# pcb_power.net
KiCad netlist of a schematic drawn in EAGLE
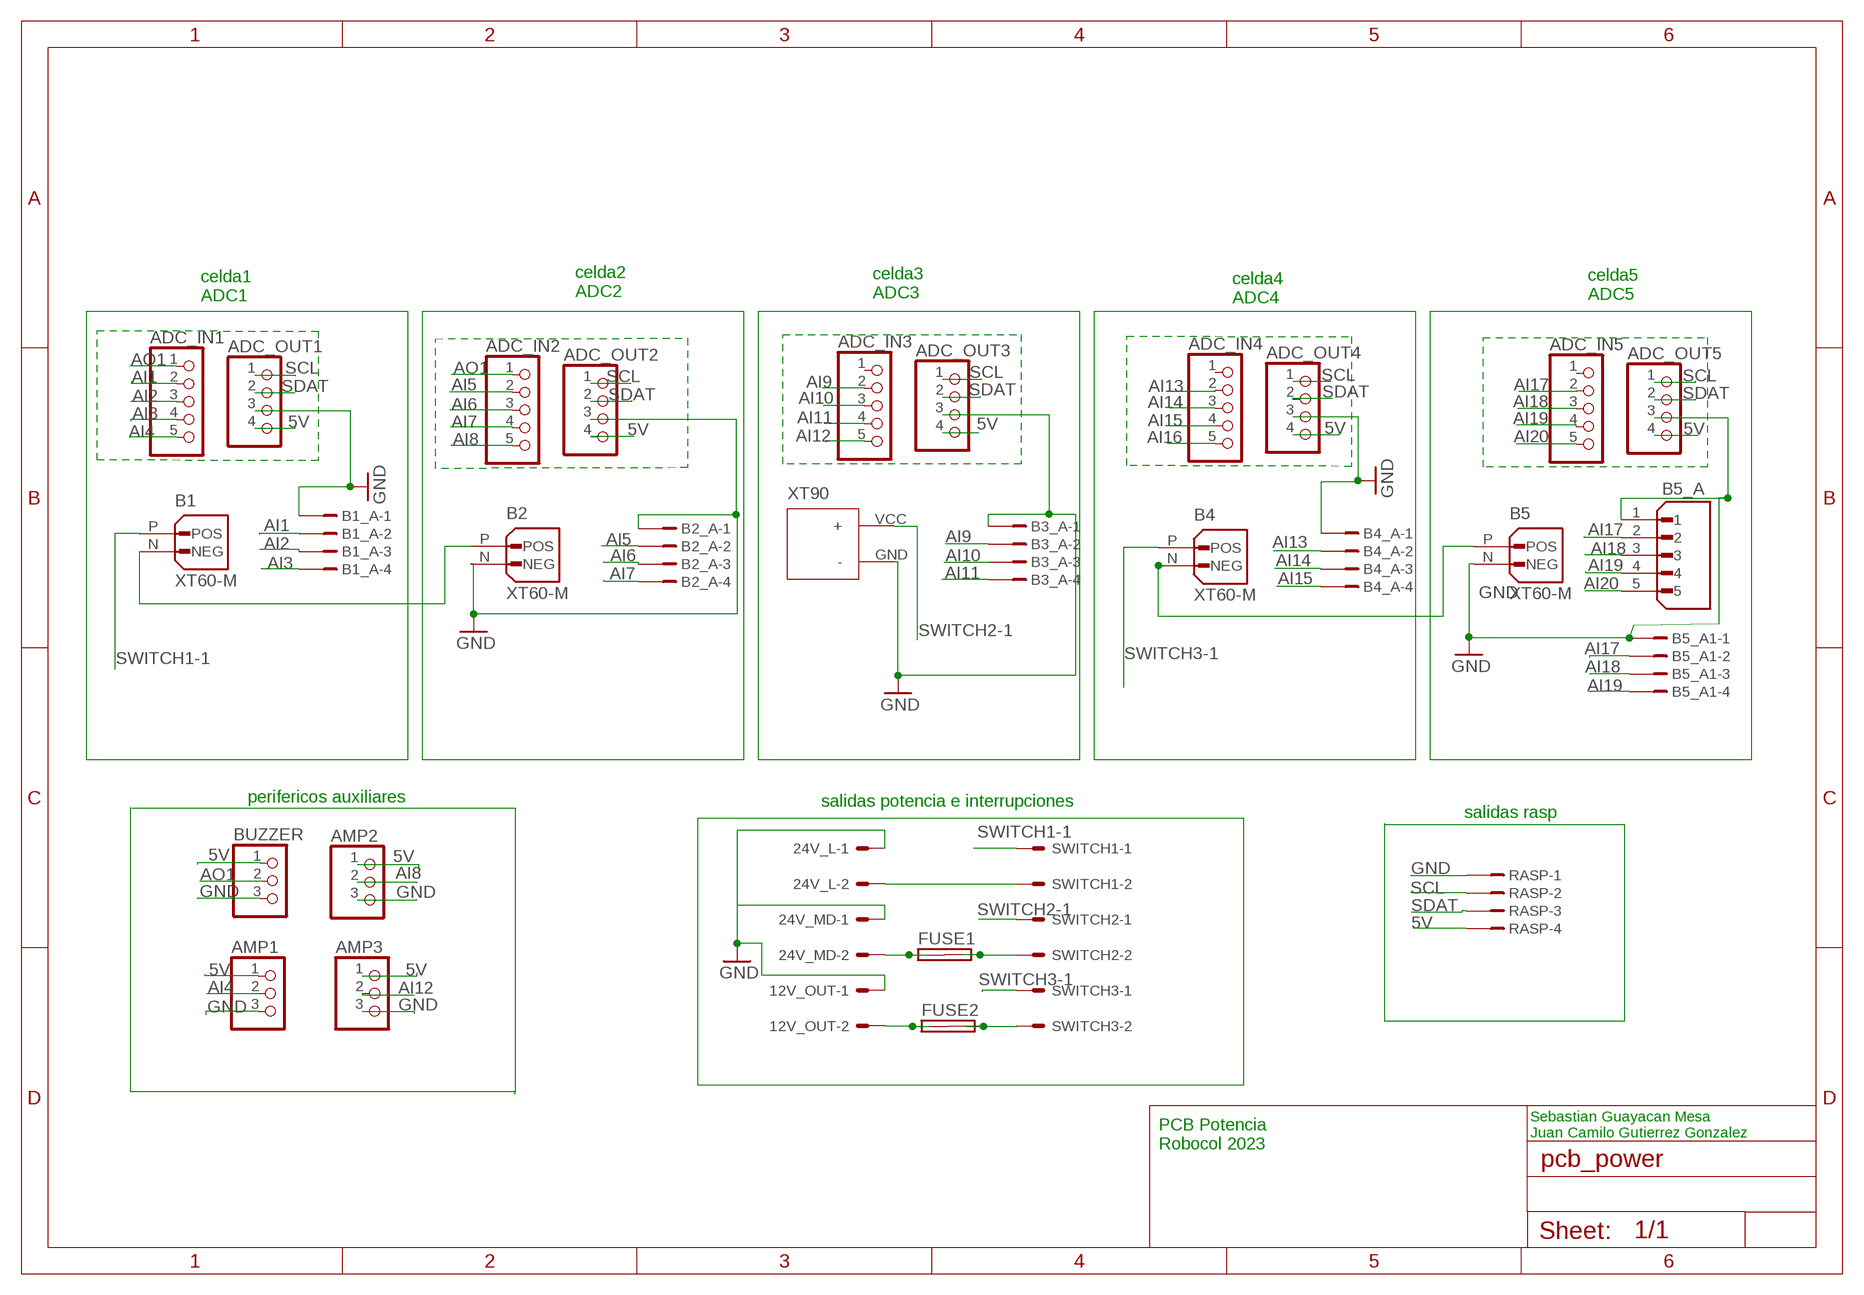
[diagram p0: schematic, sheet 1]

(export (version "E")
  (design (tool "Eeschema 10.0.6"))
  (components
    (comp (ref "12V_OUT")
      (value "5566-25569-2")
      (footprint "eagle-import:5569-2")
      (libsource (lib "eagle-import") (part "5566-25569-2"))
    )
    (comp (ref "24V_L")
      (value "5566-25569-2")
      (footprint "eagle-import:5569-2")
      (libsource (lib "eagle-import") (part "5566-25569-2"))
    )
    (comp (ref "24V_MD")
      (value "5566-25569-2")
      (footprint "eagle-import:5569-2")
      (libsource (lib "eagle-import") (part "5566-25569-2"))
    )
    (comp (ref "ADC_IN1")
      (value "PINHD-1X5")
      (footprint "eagle-import:1X05")
      (libsource (lib "eagle-import") (part "PINHD-1X5"))
    )
    (comp (ref "ADC_IN2")
      (value "PINHD-1X5")
      (footprint "eagle-import:1X05")
      (libsource (lib "eagle-import") (part "PINHD-1X5"))
    )
    (comp (ref "ADC_IN3")
      (value "PINHD-1X5")
      (footprint "eagle-import:1X05")
      (libsource (lib "eagle-import") (part "PINHD-1X5"))
    )
    (comp (ref "ADC_IN4")
      (value "PINHD-1X5")
      (footprint "eagle-import:1X05")
      (libsource (lib "eagle-import") (part "PINHD-1X5"))
    )
    (comp (ref "ADC_IN5")
      (value "PINHD-1X5")
      (footprint "eagle-import:1X05")
      (libsource (lib "eagle-import") (part "PINHD-1X5"))
    )
    (comp (ref "ADC_OUT1")
      (value "PINHD-1X4")
      (footprint "eagle-import:1X04")
      (libsource (lib "eagle-import") (part "PINHD-1X4"))
    )
    (comp (ref "ADC_OUT2")
      (value "PINHD-1X4")
      (footprint "eagle-import:1X04")
      (libsource (lib "eagle-import") (part "PINHD-1X4"))
    )
    (comp (ref "ADC_OUT3")
      (value "PINHD-1X4")
      (footprint "eagle-import:1X04")
      (libsource (lib "eagle-import") (part "PINHD-1X4"))
    )
    (comp (ref "ADC_OUT4")
      (value "PINHD-1X4")
      (footprint "eagle-import:1X04")
      (libsource (lib "eagle-import") (part "PINHD-1X4"))
    )
    (comp (ref "ADC_OUT5")
      (value "PINHD-1X4")
      (footprint "eagle-import:1X04")
      (libsource (lib "eagle-import") (part "PINHD-1X4"))
    )
    (comp (ref "AMP1")
      (value "PINHD-1X3")
      (footprint "eagle-import:1X03")
      (libsource (lib "eagle-import") (part "PINHD-1X3"))
    )
    (comp (ref "AMP2")
      (value "PINHD-1X3")
      (footprint "eagle-import:1X03")
      (libsource (lib "eagle-import") (part "PINHD-1X3"))
    )
    (comp (ref "AMP3")
      (value "PINHD-1X3")
      (footprint "eagle-import:1X03")
      (libsource (lib "eagle-import") (part "PINHD-1X3"))
    )
    (comp (ref "B1")
      (value "XT60-M")
      (footprint "eagle-import:AMASS_XT60-M")
      (fields (field (name "MF") "AMASS"))
      (libsource (lib "eagle-import") (part "XT60-M"))
    )
    (comp (ref "B1_A")
      (value "B4B-ZR")
      (footprint "eagle-import:B4B-ZR")
      (fields (field (name "MF") "FARNELL") (field (name "MPN") "B4B-ZR(LF)(SN)"))
      (libsource (lib "eagle-import") (part "?4B-ZRB"))
    )
    (comp (ref "B2")
      (value "XT60-M")
      (footprint "eagle-import:AMASS_XT60-M")
      (fields (field (name "MF") "AMASS"))
      (libsource (lib "eagle-import") (part "XT60-M"))
    )
    (comp (ref "B2_A")
      (value "B4B-ZR")
      (footprint "eagle-import:B4B-ZR")
      (fields (field (name "MF") "FARNELL") (field (name "MPN") "B4B-ZR(LF)(SN)"))
      (libsource (lib "eagle-import") (part "?4B-ZRB"))
    )
    (comp (ref "B3")
      (value "XT90")
      (footprint "eagle-import:XT90_PADS")
      (libsource (lib "eagle-import") (part "XT90"))
    )
    (comp (ref "B3_A")
      (value "B4B-ZR")
      (footprint "eagle-import:B4B-ZR")
      (fields (field (name "MF") "FARNELL") (field (name "MPN") "B4B-ZR(LF)(SN)"))
      (libsource (lib "eagle-import") (part "?4B-ZRB"))
    )
    (comp (ref "B4")
      (value "XT60-M")
      (footprint "eagle-import:AMASS_XT60-M")
      (fields (field (name "MF") "AMASS"))
      (libsource (lib "eagle-import") (part "XT60-M"))
    )
    (comp (ref "B4_A")
      (value "B4B-ZR")
      (footprint "eagle-import:B4B-ZR")
      (fields (field (name "MF") "FARNELL") (field (name "MPN") "B4B-ZR(LF)(SN)"))
      (libsource (lib "eagle-import") (part "?4B-ZRB"))
    )
    (comp (ref "B5")
      (value "XT60-M")
      (footprint "eagle-import:AMASS_XT60-M")
      (fields (field (name "MF") "AMASS"))
      (libsource (lib "eagle-import") (part "XT60-M"))
    )
    (comp (ref "B5_A")
      (value "B5B-ZR(LF)(SN)")
      (footprint "eagle-import:JST_B5B-ZR(LF)(SN)")
      (fields (field (name "MF") "JST") (field (name "MP") "B5B-ZR (LF)(SN)"))
      (libsource (lib "eagle-import") (part "B5B-ZR(LF)(SN)"))
    )
    (comp (ref "B5_A1")
      (value "B4B-ZR")
      (footprint "eagle-import:B4B-ZR")
      (fields (field (name "MF") "FARNELL") (field (name "MPN") "B4B-ZR(LF)(SN)"))
      (libsource (lib "eagle-import") (part "?4B-ZRB"))
    )
    (comp (ref "BUZZER")
      (value "PINHD-1X3")
      (footprint "eagle-import:1X03")
      (libsource (lib "eagle-import") (part "PINHD-1X3"))
    )
    (comp (ref "FUSE1")
      (value "SHK20L")
      (footprint "eagle-import:SHK20L")
      (libsource (lib "eagle-import") (part "SHK20L"))
    )
    (comp (ref "FUSE2")
      (value "SHK20L")
      (footprint "eagle-import:SHK20L")
      (libsource (lib "eagle-import") (part "SHK20L"))
    )
    (comp (ref "RASP")
      (value "B4B-ZR")
      (footprint "eagle-import:B4B-ZR")
      (fields (field (name "MF") "FARNELL") (field (name "MPN") "B4B-ZR(LF)(SN)"))
      (libsource (lib "eagle-import") (part "?4B-ZRB"))
    )
    (comp (ref "SWITCH1")
      (value "5566-25569-2")
      (footprint "eagle-import:5569-2")
      (libsource (lib "eagle-import") (part "5566-25569-2"))
    )
    (comp (ref "SWITCH2")
      (value "5566-25569-2")
      (footprint "eagle-import:5569-2")
      (libsource (lib "eagle-import") (part "5566-25569-2"))
    )
    (comp (ref "SWITCH3")
      (value "5566-25569-2")
      (footprint "eagle-import:5569-2")
      (libsource (lib "eagle-import") (part "5566-25569-2"))
    )
  )
  (nets
    (net (code "1") (name "/5V") (class "Default")
      (node (ref "ADC_OUT1") (pin "4") (pinfunction "4_4") (pintype "passive"))
      (node (ref "ADC_OUT2") (pin "4") (pinfunction "4_4") (pintype "passive"))
      (node (ref "ADC_OUT3") (pin "4") (pinfunction "4_4") (pintype "passive"))
      (node (ref "ADC_OUT4") (pin "4") (pinfunction "4_4") (pintype "passive"))
      (node (ref "ADC_OUT5") (pin "4") (pinfunction "4_4") (pintype "passive"))
      (node (ref "AMP1") (pin "1") (pinfunction "1_1") (pintype "passive"))
      (node (ref "AMP2") (pin "1") (pinfunction "1_1") (pintype "passive"))
      (node (ref "AMP3") (pin "1") (pinfunction "1_1") (pintype "passive"))
      (node (ref "BUZZER") (pin "1") (pinfunction "1_1") (pintype "passive"))
      (node (ref "RASP") (pin "4") (pinfunction "1_4") (pintype "passive"))
    )
    (net (code "2") (name "/AI1") (class "Default")
      (node (ref "ADC_IN1") (pin "2") (pinfunction "2_2") (pintype "passive"))
      (node (ref "B1_A") (pin "2") (pinfunction "1_2") (pintype "passive"))
    )
    (net (code "3") (name "/AI2") (class "Default")
      (node (ref "ADC_IN1") (pin "3") (pinfunction "3_3") (pintype "passive"))
      (node (ref "B1_A") (pin "3") (pinfunction "1_3") (pintype "passive"))
    )
    (net (code "4") (name "/AI3") (class "Default")
      (node (ref "ADC_IN1") (pin "4") (pinfunction "4_4") (pintype "passive"))
      (node (ref "B1_A") (pin "4") (pinfunction "1_4") (pintype "passive"))
    )
    (net (code "5") (name "/AI4") (class "Default")
      (node (ref "ADC_IN1") (pin "5") (pinfunction "5_5") (pintype "passive"))
      (node (ref "AMP1") (pin "2") (pinfunction "2_2") (pintype "passive"))
    )
    (net (code "6") (name "/AI5") (class "Default")
      (node (ref "ADC_IN2") (pin "2") (pinfunction "2_2") (pintype "passive"))
      (node (ref "B2_A") (pin "2") (pinfunction "1_2") (pintype "passive"))
    )
    (net (code "7") (name "/AI6") (class "Default")
      (node (ref "ADC_IN2") (pin "3") (pinfunction "3_3") (pintype "passive"))
      (node (ref "B2_A") (pin "3") (pinfunction "1_3") (pintype "passive"))
    )
    (net (code "8") (name "/AI7") (class "Default")
      (node (ref "ADC_IN2") (pin "4") (pinfunction "4_4") (pintype "passive"))
      (node (ref "B2_A") (pin "4") (pinfunction "1_4") (pintype "passive"))
    )
    (net (code "9") (name "/AI8") (class "Default")
      (node (ref "ADC_IN2") (pin "5") (pinfunction "5_5") (pintype "passive"))
      (node (ref "AMP2") (pin "2") (pinfunction "2_2") (pintype "passive"))
    )
    (net (code "10") (name "/AI9") (class "Default")
      (node (ref "ADC_IN3") (pin "2") (pinfunction "2_2") (pintype "passive"))
      (node (ref "B3_A") (pin "2") (pinfunction "1_2") (pintype "passive"))
    )
    (net (code "11") (name "/AI10") (class "Default")
      (node (ref "ADC_IN3") (pin "3") (pinfunction "3_3") (pintype "passive"))
      (node (ref "B3_A") (pin "3") (pinfunction "1_3") (pintype "passive"))
    )
    (net (code "12") (name "/AI11") (class "Default")
      (node (ref "ADC_IN3") (pin "4") (pinfunction "4_4") (pintype "passive"))
      (node (ref "B3_A") (pin "4") (pinfunction "1_4") (pintype "passive"))
    )
    (net (code "13") (name "/AI12") (class "Default")
      (node (ref "ADC_IN3") (pin "5") (pinfunction "5_5") (pintype "passive"))
      (node (ref "AMP3") (pin "2") (pinfunction "2_2") (pintype "passive"))
    )
    (net (code "14") (name "/AI13") (class "Default")
      (node (ref "ADC_IN4") (pin "2") (pinfunction "2_2") (pintype "passive"))
      (node (ref "B4_A") (pin "2") (pinfunction "1_2") (pintype "passive"))
    )
    (net (code "15") (name "/AI14") (class "Default")
      (node (ref "ADC_IN4") (pin "3") (pinfunction "3_3") (pintype "passive"))
      (node (ref "B4_A") (pin "3") (pinfunction "1_3") (pintype "passive"))
    )
    (net (code "16") (name "/AI15") (class "Default")
      (node (ref "ADC_IN4") (pin "4") (pinfunction "4_4") (pintype "passive"))
      (node (ref "B4_A") (pin "4") (pinfunction "1_4") (pintype "passive"))
    )
    (net (code "17") (name "/AI16") (class "Default")
      (node (ref "ADC_IN4") (pin "5") (pinfunction "5_5") (pintype "passive"))
    )
    (net (code "18") (name "/AI17") (class "Default")
      (node (ref "ADC_IN5") (pin "2") (pinfunction "2_2") (pintype "passive"))
      (node (ref "B5_A") (pin "2") (pinfunction "2_2") (pintype "passive"))
      (node (ref "B5_A1") (pin "2") (pinfunction "1_2") (pintype "passive"))
    )
    (net (code "19") (name "/AI18") (class "Default")
      (node (ref "ADC_IN5") (pin "3") (pinfunction "3_3") (pintype "passive"))
      (node (ref "B5_A") (pin "3") (pinfunction "3_3") (pintype "passive"))
      (node (ref "B5_A1") (pin "3") (pinfunction "1_3") (pintype "passive"))
    )
    (net (code "20") (name "/AI19") (class "Default")
      (node (ref "ADC_IN5") (pin "4") (pinfunction "4_4") (pintype "passive"))
      (node (ref "B5_A") (pin "4") (pinfunction "4_4") (pintype "passive"))
      (node (ref "B5_A1") (pin "4") (pinfunction "1_4") (pintype "passive"))
    )
    (net (code "21") (name "/AI20") (class "Default")
      (node (ref "ADC_IN5") (pin "5") (pinfunction "5_5") (pintype "passive"))
      (node (ref "B5_A") (pin "5") (pinfunction "5_5") (pintype "passive"))
    )
    (net (code "22") (name "/AO1") (class "Default")
      (node (ref "ADC_IN1") (pin "1") (pinfunction "1_1") (pintype "passive"))
      (node (ref "ADC_IN2") (pin "1") (pinfunction "1_1") (pintype "passive"))
      (node (ref "BUZZER") (pin "2") (pinfunction "2_2") (pintype "passive"))
    )
    (net (code "23") (name "/SCL") (class "Default")
      (node (ref "ADC_OUT1") (pin "1") (pinfunction "1_1") (pintype "passive"))
      (node (ref "ADC_OUT2") (pin "1") (pinfunction "1_1") (pintype "passive"))
      (node (ref "ADC_OUT3") (pin "1") (pinfunction "1_1") (pintype "passive"))
      (node (ref "ADC_OUT4") (pin "1") (pinfunction "1_1") (pintype "passive"))
      (node (ref "ADC_OUT5") (pin "1") (pinfunction "1_1") (pintype "passive"))
      (node (ref "RASP") (pin "2") (pinfunction "1_2") (pintype "passive"))
    )
    (net (code "24") (name "/SDAT") (class "Default")
      (node (ref "ADC_OUT1") (pin "2") (pinfunction "2_2") (pintype "passive"))
      (node (ref "ADC_OUT2") (pin "2") (pinfunction "2_2") (pintype "passive"))
      (node (ref "ADC_OUT3") (pin "2") (pinfunction "2_2") (pintype "passive"))
      (node (ref "ADC_OUT4") (pin "2") (pinfunction "2_2") (pintype "passive"))
      (node (ref "ADC_OUT5") (pin "2") (pinfunction "2_2") (pintype "passive"))
      (node (ref "RASP") (pin "3") (pinfunction "1_3") (pintype "passive"))
    )
    (net (code "25") (name "/SWITCH1-1") (class "Default")
      (node (ref "B1") (pin "P") (pinfunction "POS_P") (pintype "passive"))
      (node (ref "SWITCH1") (pin "1") (pinfunction "S_1") (pintype "passive"))
    )
    (net (code "26") (name "/SWITCH2-1") (class "Default")
      (node (ref "B3") (pin "VCC") (pinfunction "+_VCC") (pintype "power_in"))
      (node (ref "SWITCH2") (pin "1") (pinfunction "S_1") (pintype "passive"))
    )
    (net (code "27") (name "/SWITCH3-1") (class "Default")
      (node (ref "B4") (pin "P") (pinfunction "POS_P") (pintype "passive"))
      (node (ref "SWITCH3") (pin "1") (pinfunction "S_1") (pintype "passive"))
    )
    (net (code "28") (name "GND") (class "Default")
      (node (ref "12V_OUT") (pin "1") (pinfunction "S_1") (pintype "passive"))
      (node (ref "24V_L") (pin "1") (pinfunction "S_1") (pintype "passive"))
      (node (ref "24V_MD") (pin "1") (pinfunction "S_1") (pintype "passive"))
      (node (ref "ADC_OUT1") (pin "3") (pinfunction "3_3") (pintype "passive"))
      (node (ref "ADC_OUT2") (pin "3") (pinfunction "3_3") (pintype "passive"))
      (node (ref "ADC_OUT3") (pin "3") (pinfunction "3_3") (pintype "passive"))
      (node (ref "ADC_OUT4") (pin "3") (pinfunction "3_3") (pintype "passive"))
      (node (ref "ADC_OUT5") (pin "3") (pinfunction "3_3") (pintype "passive"))
      (node (ref "AMP1") (pin "3") (pinfunction "3_3") (pintype "passive"))
      (node (ref "AMP2") (pin "3") (pinfunction "3_3") (pintype "passive"))
      (node (ref "AMP3") (pin "3") (pinfunction "3_3") (pintype "passive"))
      (node (ref "B1_A") (pin "1") (pinfunction "1_1") (pintype "passive"))
      (node (ref "B2") (pin "N") (pinfunction "NEG_N") (pintype "passive"))
      (node (ref "B2_A") (pin "1") (pinfunction "1_1") (pintype "passive"))
      (node (ref "B3") (pin "GND") (pinfunction "-_GND") (pintype "power_in"))
      (node (ref "B3_A") (pin "1") (pinfunction "1_1") (pintype "passive"))
      (node (ref "B4_A") (pin "1") (pinfunction "1_1") (pintype "passive"))
      (node (ref "B5") (pin "N") (pinfunction "NEG_N") (pintype "passive"))
      (node (ref "B5_A") (pin "1") (pinfunction "1_1") (pintype "passive"))
      (node (ref "B5_A1") (pin "1") (pinfunction "1_1") (pintype "passive"))
      (node (ref "BUZZER") (pin "3") (pinfunction "3_3") (pintype "passive"))
      (node (ref "RASP") (pin "1") (pinfunction "1_1") (pintype "passive"))
    )
    (net (code "29") (name "Net-(12V_OUTB-S)") (class "Default")
      (node (ref "12V_OUT") (pin "2") (pinfunction "S_2") (pintype "passive"))
      (node (ref "FUSE2") (pin "1A") (pinfunction "1A_1A") (pintype "passive"))
      (node (ref "FUSE2") (pin "1B") (pinfunction "1B_1B") (pintype "passive"))
    )
    (net (code "30") (name "Net-(24V_LB-S)") (class "Default")
      (node (ref "24V_L") (pin "2") (pinfunction "S_2") (pintype "passive"))
      (node (ref "SWITCH1") (pin "2") (pinfunction "S_2") (pintype "passive"))
    )
    (net (code "31") (name "Net-(24V_MDB-S)") (class "Default")
      (node (ref "24V_MD") (pin "2") (pinfunction "S_2") (pintype "passive"))
      (node (ref "FUSE1") (pin "1A") (pinfunction "1A_1A") (pintype "passive"))
      (node (ref "FUSE1") (pin "1B") (pinfunction "1B_1B") (pintype "passive"))
    )
    (net (code "32") (name "Net-(B1-NEG)") (class "Default")
      (node (ref "B1") (pin "N") (pinfunction "NEG_N") (pintype "passive"))
      (node (ref "B2") (pin "P") (pinfunction "POS_P") (pintype "passive"))
    )
    (net (code "33") (name "Net-(B4-NEG)") (class "Default")
      (node (ref "B4") (pin "N") (pinfunction "NEG_N") (pintype "passive"))
      (node (ref "B5") (pin "P") (pinfunction "POS_P") (pintype "passive"))
    )
    (net (code "34") (name "Net-(SWITCH2B-S)") (class "Default")
      (node (ref "FUSE1") (pin "2A") (pinfunction "2A_2A") (pintype "passive"))
      (node (ref "FUSE1") (pin "2B") (pinfunction "2B_2B") (pintype "passive"))
      (node (ref "SWITCH2") (pin "2") (pinfunction "S_2") (pintype "passive"))
    )
    (net (code "35") (name "Net-(SWITCH3B-S)") (class "Default")
      (node (ref "FUSE2") (pin "2A") (pinfunction "2A_2A") (pintype "passive"))
      (node (ref "FUSE2") (pin "2B") (pinfunction "2B_2B") (pintype "passive"))
      (node (ref "SWITCH3") (pin "2") (pinfunction "S_2") (pintype "passive"))
    )
    (net (code "36") (name "unconnected-(ADC_IN3-Pad1)") (class "Default")
      (node (ref "ADC_IN3") (pin "1") (pinfunction "1_1") (pintype "passive"))
    )
    (net (code "37") (name "unconnected-(ADC_IN4-Pad1)") (class "Default")
      (node (ref "ADC_IN4") (pin "1") (pinfunction "1_1") (pintype "passive"))
    )
    (net (code "38") (name "unconnected-(ADC_IN5-Pad1)") (class "Default")
      (node (ref "ADC_IN5") (pin "1") (pinfunction "1_1") (pintype "passive"))
    )
  )
)
